# 5S.net
KiCad netlist of a schematic drawn in EAGLE
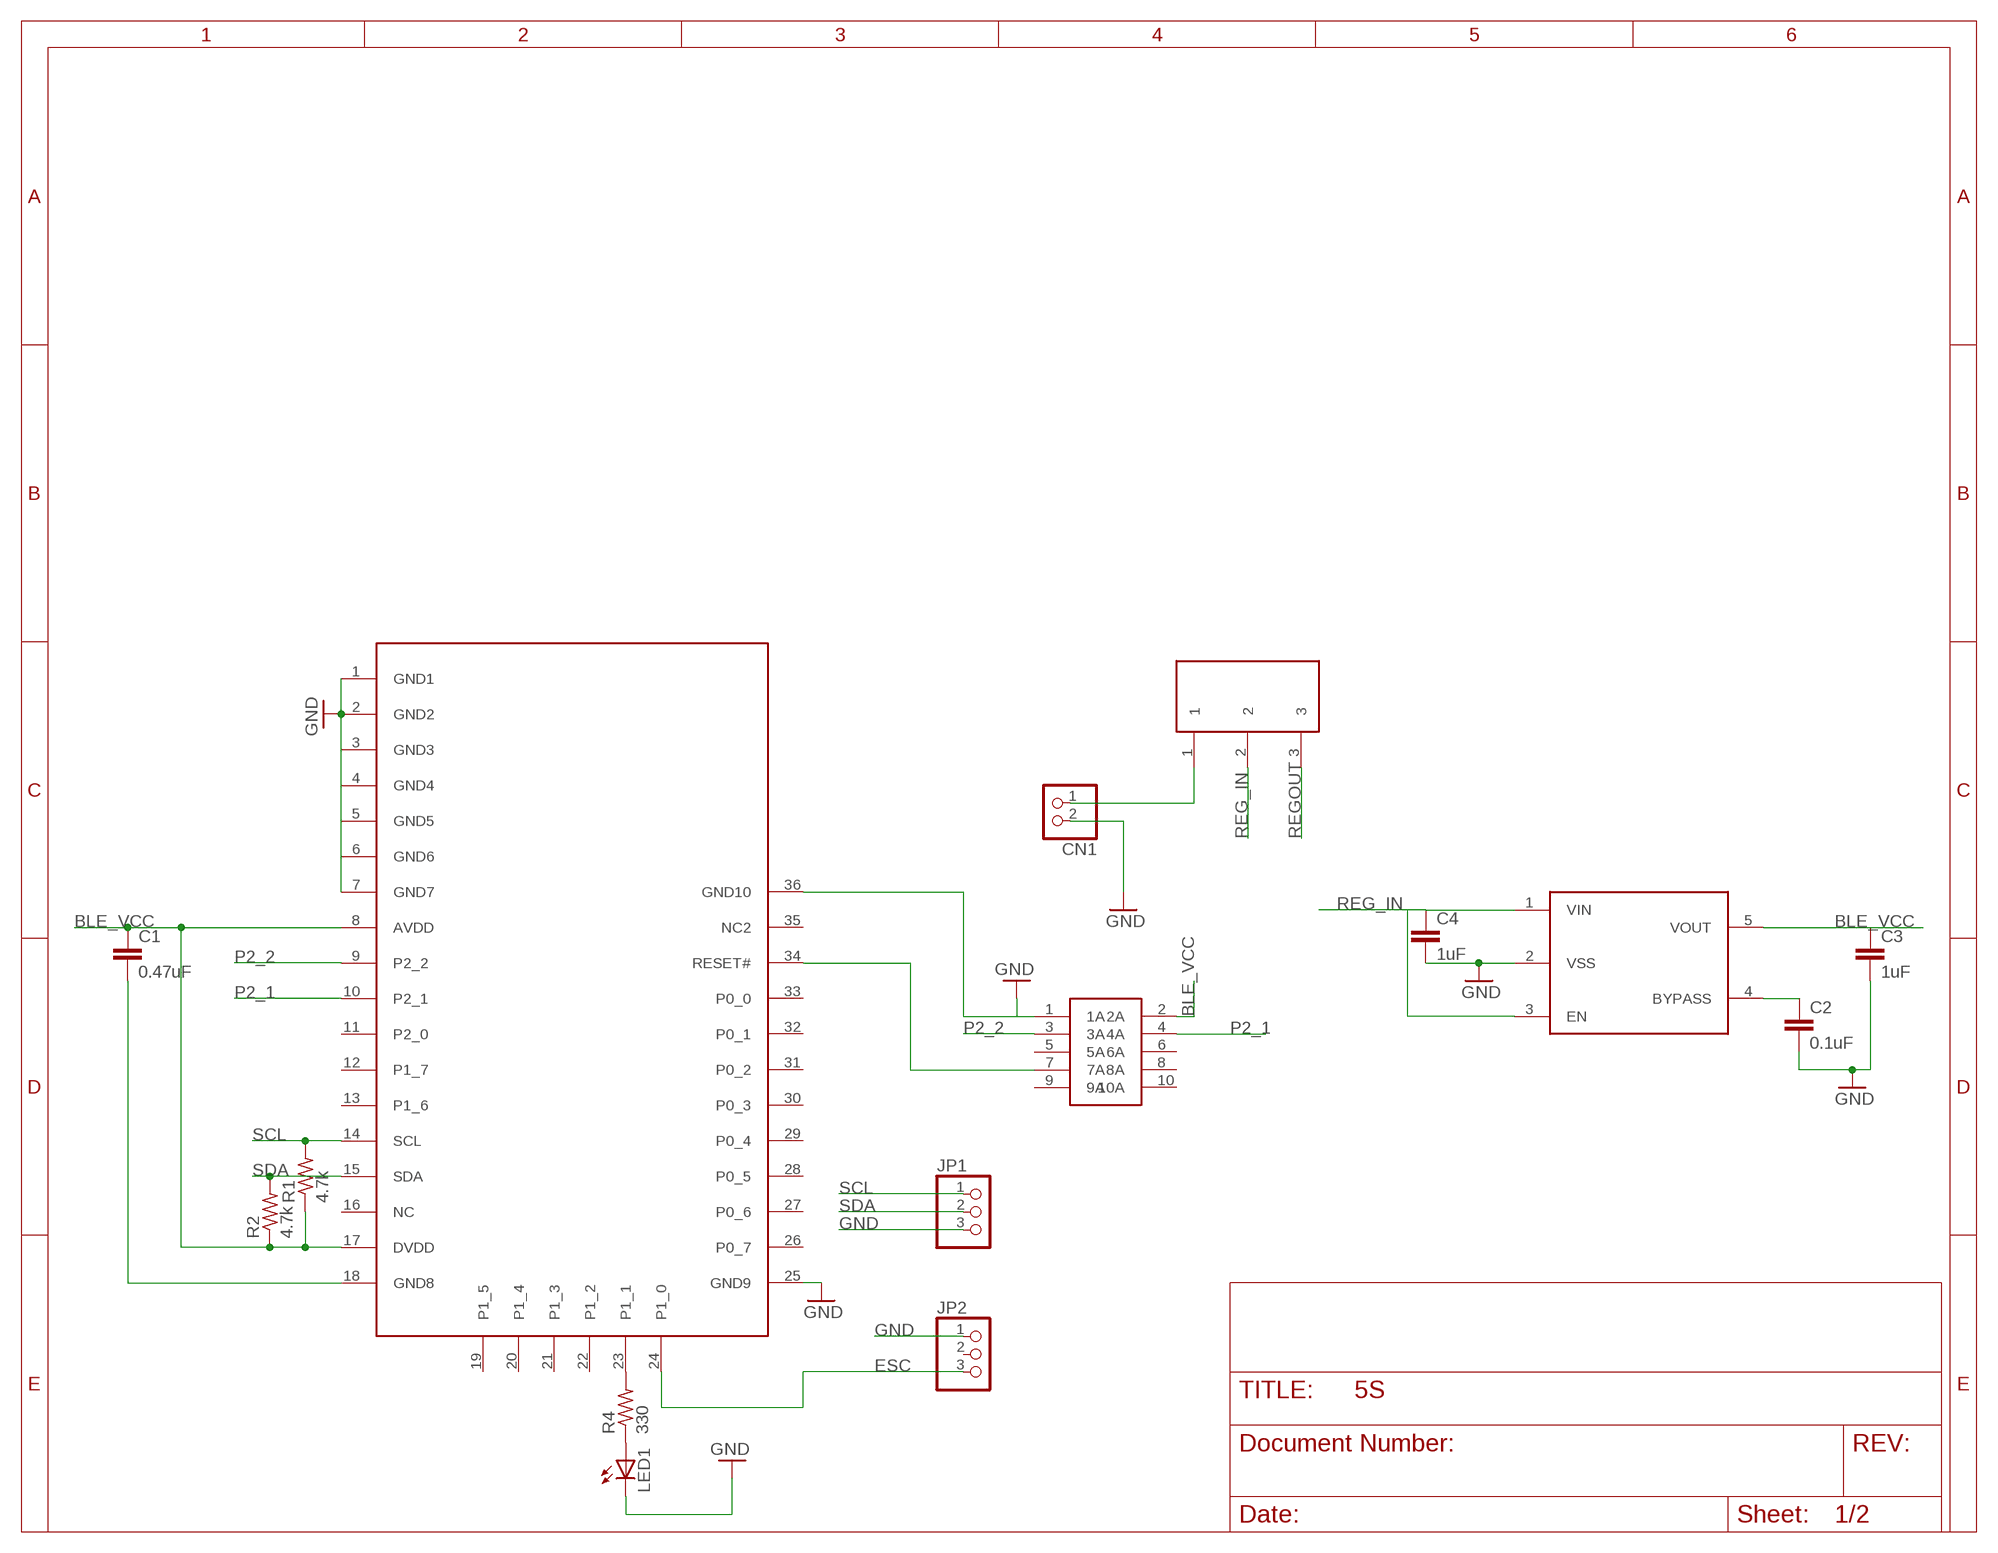
[diagram p0: schematic, sheet 1]
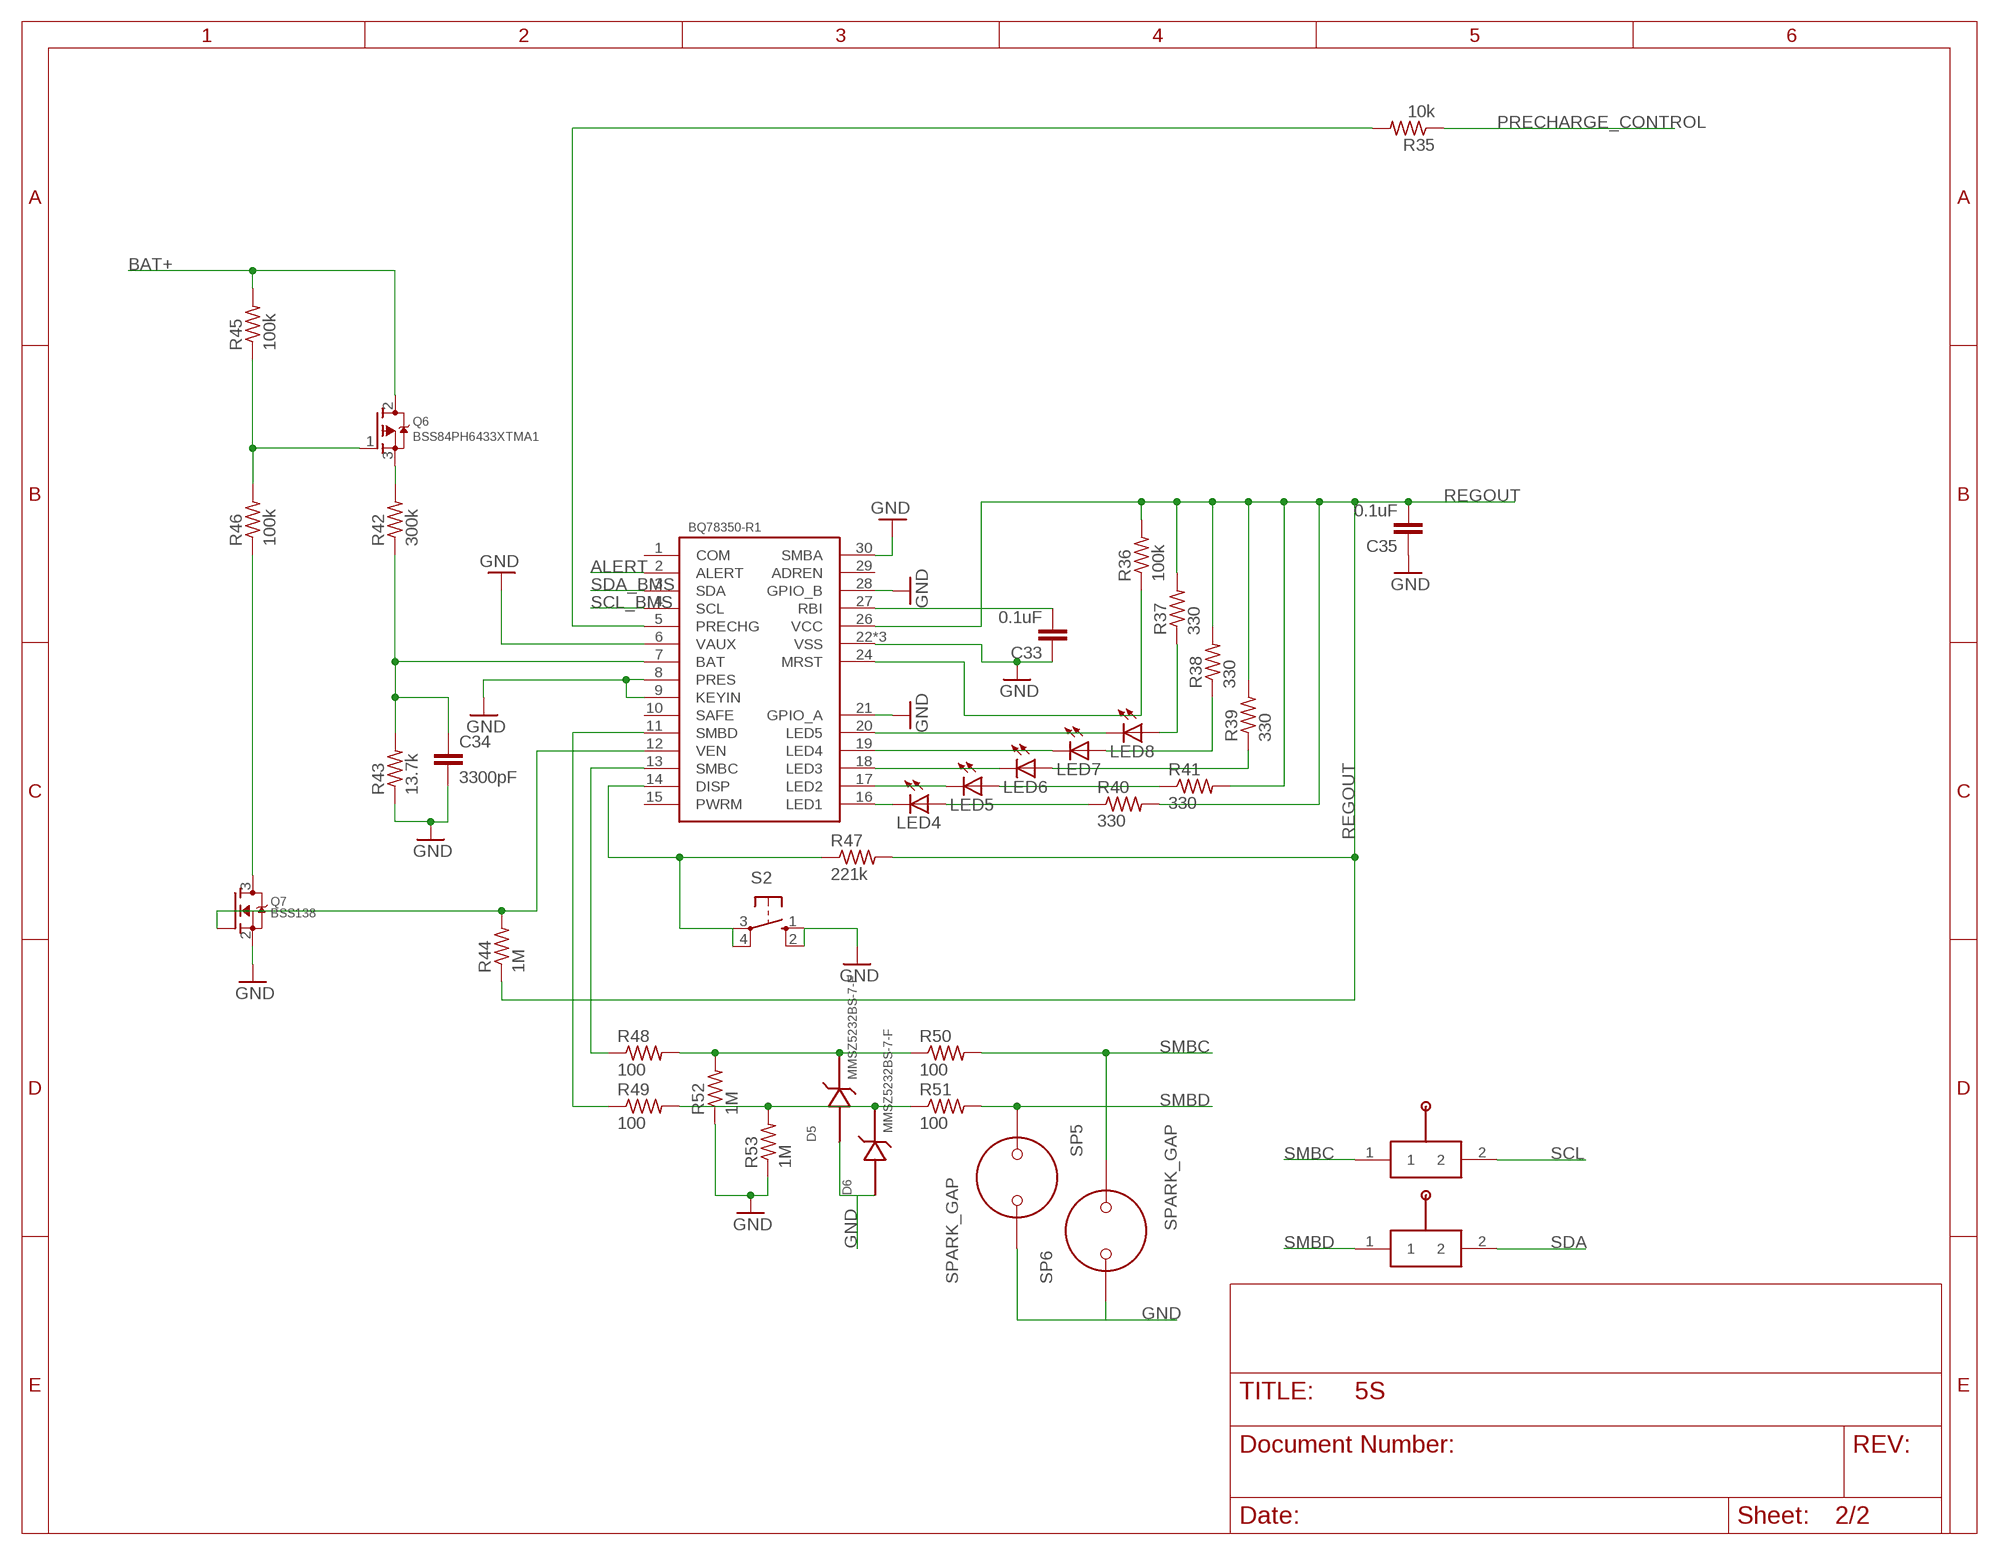
[diagram p1: schematic, sheet 2, part 1 of 2]
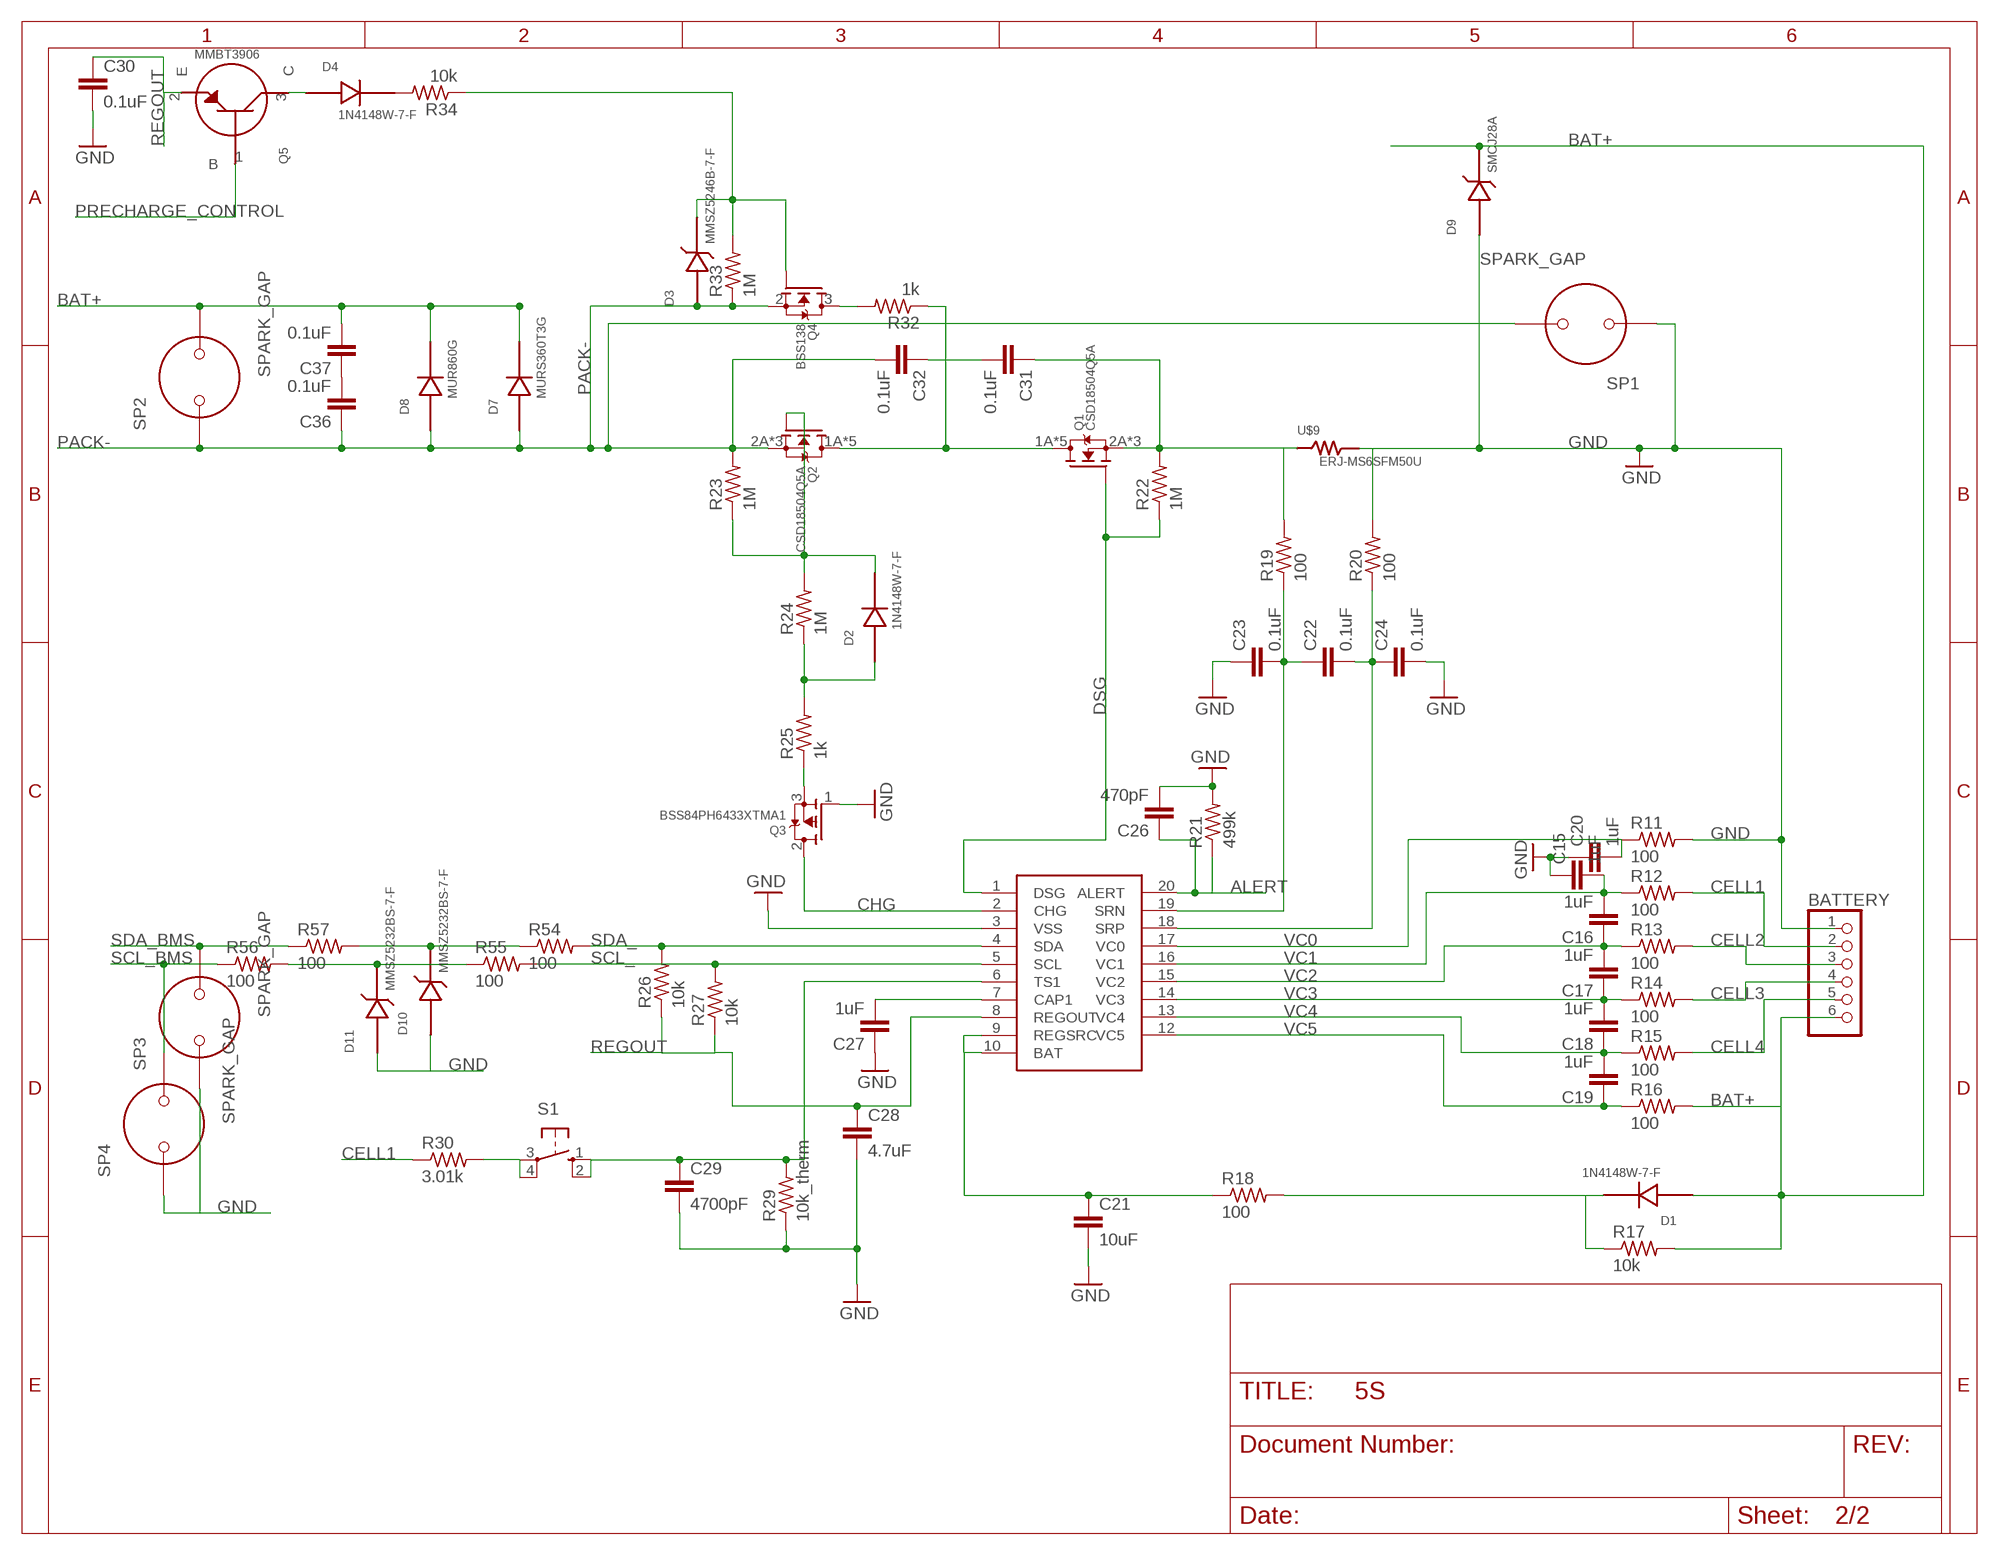
[diagram p2: schematic, sheet 2, part 2 of 2]

(export (version "E")
  (design (tool "Eeschema 10.0.6"))
  (components
    (comp (ref "C1")
      (value "0.47uF")
      (footprint "eagle-import:C0402")
      (libsource (lib "eagle-import") (part "C-EUC0402"))
    )
    (comp (ref "C2")
      (value "0.1uF")
      (footprint "eagle-import:C0402")
      (libsource (lib "eagle-import") (part "C-EUC0402"))
    )
    (comp (ref "C3")
      (value "1uF")
      (footprint "eagle-import:C0402")
      (libsource (lib "eagle-import") (part "C-EUC0402"))
    )
    (comp (ref "C4")
      (value "1uF")
      (footprint "eagle-import:C0402")
      (libsource (lib "eagle-import") (part "C-EUC0402"))
    )
    (comp (ref "CN1")
      (value "JST_2PIN-THM")
      (footprint "eagle-import:JST-PH-2-THM")
      (libsource (lib "eagle-import") (part "JST_2PIN-THM"))
    )
    (comp (ref "JP1")
      (value "PINHD-1X3")
      (footprint "eagle-import:1X03")
      (libsource (lib "eagle-import") (part "PINHD-1X3"))
    )
    (comp (ref "JP2")
      (value "PINHD-1X3")
      (footprint "eagle-import:1X03")
      (libsource (lib "eagle-import") (part "PINHD-1X3"))
    )
    (comp (ref "LED1")
      (value "LEDCHIP-LED0805")
      (footprint "eagle-import:CHIP-LED0805")
      (libsource (lib "eagle-import") (part "LEDCHIP-LED0805"))
    )
    (comp (ref "R1")
      (value "4.7k")
      (footprint "eagle-import:R0402")
      (libsource (lib "eagle-import") (part "R-US_R0402"))
    )
    (comp (ref "R2")
      (value "4.7k")
      (footprint "eagle-import:R0402")
      (libsource (lib "eagle-import") (part "R-US_R0402"))
    )
    (comp (ref "R4")
      (value "330")
      (footprint "eagle-import:R0402")
      (libsource (lib "eagle-import") (part "R-US_R0402"))
    )
    (comp (ref "U$1")
      (value "BLE113")
      (footprint "eagle-import:BLUEGIGA")
      (libsource (lib "eagle-import") (part "BLE113"))
    )
    (comp (ref "U$2")
      (value "RIBBON_10POS_MALE")
      (footprint "eagle-import:RIBBON_10POS_MALE")
      (libsource (lib "eagle-import") (part "RIBBON_10POS_MALE"))
    )
    (comp (ref "U$4")
      (value "SPDT_THRU")
      (footprint "eagle-import:SPDT_THRU")
      (libsource (lib "eagle-import") (part "SPDT_THRU"))
    )
    (comp (ref "U$5")
      (value "LP3985")
      (footprint "eagle-import:SOT23-5L")
      (libsource (lib "eagle-import") (part "LP3985"))
    )
    (comp (ref "BATTERY")
      (value "PINHD-1X6")
      (footprint "eagle-import:1X06")
      (libsource (lib "eagle-import") (part "PINHD-1X6"))
    )
    (comp (ref "C15")
      (value "1uF")
      (footprint "eagle-import:C0805")
      (libsource (lib "eagle-import") (part "C-EUC0805"))
    )
    (comp (ref "C16")
      (value "1uF")
      (footprint "eagle-import:C0805")
      (libsource (lib "eagle-import") (part "C-EUC0805"))
    )
    (comp (ref "C17")
      (value "1uF")
      (footprint "eagle-import:C0805")
      (libsource (lib "eagle-import") (part "C-EUC0805"))
    )
    (comp (ref "C18")
      (value "1uF")
      (footprint "eagle-import:C0805")
      (libsource (lib "eagle-import") (part "C-EUC0805"))
    )
    (comp (ref "C19")
      (value "1uF")
      (footprint "eagle-import:C0805")
      (libsource (lib "eagle-import") (part "C-EUC0805"))
    )
    (comp (ref "C20")
      (value "1uF")
      (footprint "eagle-import:C0805")
      (libsource (lib "eagle-import") (part "C-EUC0805"))
    )
    (comp (ref "C21")
      (value "10uF")
      (footprint "eagle-import:C1206")
      (libsource (lib "eagle-import") (part "C-EUC1206"))
    )
    (comp (ref "C22")
      (value "0.1uF")
      (footprint "eagle-import:C0805")
      (libsource (lib "eagle-import") (part "C-EUC0805"))
    )
    (comp (ref "C23")
      (value "0.1uF")
      (footprint "eagle-import:C0805")
      (libsource (lib "eagle-import") (part "C-EUC0805"))
    )
    (comp (ref "C24")
      (value "0.1uF")
      (footprint "eagle-import:C0805")
      (libsource (lib "eagle-import") (part "C-EUC0805"))
    )
    (comp (ref "C26")
      (value "470pF")
      (footprint "eagle-import:C0805")
      (libsource (lib "eagle-import") (part "C-EUC0805"))
    )
    (comp (ref "C27")
      (value "1uF")
      (footprint "eagle-import:C0805")
      (libsource (lib "eagle-import") (part "C-EUC0805"))
    )
    (comp (ref "C28")
      (value "4.7uF")
      (footprint "eagle-import:C0805")
      (libsource (lib "eagle-import") (part "C-EUC0805"))
    )
    (comp (ref "C29")
      (value "4700pF")
      (footprint "eagle-import:C0402")
      (libsource (lib "eagle-import") (part "C-EUC0402"))
    )
    (comp (ref "C30")
      (value "0.1uF")
      (footprint "eagle-import:C0805")
      (libsource (lib "eagle-import") (part "C-EUC0805"))
    )
    (comp (ref "C31")
      (value "0.1uF")
      (footprint "eagle-import:C0805")
      (libsource (lib "eagle-import") (part "C-EUC0805"))
    )
    (comp (ref "C32")
      (value "0.1uF")
      (footprint "eagle-import:C0805")
      (libsource (lib "eagle-import") (part "C-EUC0805"))
    )
    (comp (ref "C33")
      (value "0.1uF")
      (footprint "eagle-import:C0805")
      (libsource (lib "eagle-import") (part "C-EUC0805"))
    )
    (comp (ref "C34")
      (value "3300pF")
      (footprint "eagle-import:C0402")
      (libsource (lib "eagle-import") (part "C-EUC0402"))
    )
    (comp (ref "C35")
      (value "0.1uF")
      (footprint "eagle-import:C0805")
      (libsource (lib "eagle-import") (part "C-EUC0805"))
    )
    (comp (ref "C36")
      (value "0.1uF")
      (footprint "eagle-import:C0805")
      (libsource (lib "eagle-import") (part "C-EUC0805"))
    )
    (comp (ref "C37")
      (value "0.1uF")
      (footprint "eagle-import:C0805")
      (libsource (lib "eagle-import") (part "C-EUC0805"))
    )
    (comp (ref "D1")
      (value "1N4148W-7-F")
      (footprint "eagle-import:SOD-123")
      (libsource (lib "eagle-import") (part "1N4148W-7-F"))
    )
    (comp (ref "D2")
      (value "1N4148W-7-F")
      (footprint "eagle-import:SOD-123")
      (libsource (lib "eagle-import") (part "1N4148W-7-F"))
    )
    (comp (ref "D3")
      (value "MMSZ5246B-7-F")
      (footprint "eagle-import:SOD-123")
      (libsource (lib "eagle-import") (part "MMSZ5246B-7-F"))
    )
    (comp (ref "D4")
      (value "1N4148W-7-F")
      (footprint "eagle-import:SOD-123")
      (libsource (lib "eagle-import") (part "1N4148W-7-F"))
    )
    (comp (ref "D5")
      (value "MMSZ5232BS-7-F")
      (footprint "eagle-import:SOD-323F")
      (libsource (lib "eagle-import") (part "MMSZ5232BS-7-F"))
    )
    (comp (ref "D6")
      (value "MMSZ5232BS-7-F")
      (footprint "eagle-import:SOD-323F")
      (libsource (lib "eagle-import") (part "MMSZ5232BS-7-F"))
    )
    (comp (ref "D7")
      (value "MURS360T3G")
      (footprint "eagle-import:SMC(DO-214AB)")
      (libsource (lib "eagle-import") (part "MURS360T3G"))
    )
    (comp (ref "D8")
      (value "MUR860G")
      (footprint "eagle-import:TO-220(2RA)")
      (libsource (lib "eagle-import") (part "MUR860G"))
    )
    (comp (ref "D9")
      (value "SMCJ28A")
      (footprint "eagle-import:SMC(DO-214AB)")
      (libsource (lib "eagle-import") (part "SMCJ28A"))
    )
    (comp (ref "D10")
      (value "MMSZ5232BS-7-F")
      (footprint "eagle-import:SOD-323F")
      (libsource (lib "eagle-import") (part "MMSZ5232BS-7-F"))
    )
    (comp (ref "D11")
      (value "MMSZ5232BS-7-F")
      (footprint "eagle-import:SOD-323F")
      (libsource (lib "eagle-import") (part "MMSZ5232BS-7-F"))
    )
    (comp (ref "LED4")
      (value "LEDCHIPLED_0805")
      (footprint "eagle-import:CHIPLED_0805")
      (libsource (lib "eagle-import") (part "LEDCHIPLED_0805"))
    )
    (comp (ref "LED5")
      (value "LEDCHIPLED_0805")
      (footprint "eagle-import:CHIPLED_0805")
      (libsource (lib "eagle-import") (part "LEDCHIPLED_0805"))
    )
    (comp (ref "LED6")
      (value "LEDCHIPLED_0805")
      (footprint "eagle-import:CHIPLED_0805")
      (libsource (lib "eagle-import") (part "LEDCHIPLED_0805"))
    )
    (comp (ref "LED7")
      (value "LEDCHIPLED_0805")
      (footprint "eagle-import:CHIPLED_0805")
      (libsource (lib "eagle-import") (part "LEDCHIPLED_0805"))
    )
    (comp (ref "LED8")
      (value "LEDCHIPLED_0805")
      (footprint "eagle-import:CHIPLED_0805")
      (libsource (lib "eagle-import") (part "LEDCHIPLED_0805"))
    )
    (comp (ref "Q1")
      (value "CSD18504Q5A")
      (footprint "eagle-import:Q5A")
      (libsource (lib "eagle-import") (part "CSD18504Q5A"))
    )
    (comp (ref "Q2")
      (value "CSD18504Q5A")
      (footprint "eagle-import:Q5A")
      (libsource (lib "eagle-import") (part "CSD18504Q5A"))
    )
    (comp (ref "Q3")
      (value "BSS84PH6433XTMA1")
      (footprint "eagle-import:SOT23-3")
      (libsource (lib "eagle-import") (part "BSS84PH6433XTMA1"))
    )
    (comp (ref "Q4")
      (value "BSS138")
      (footprint "eagle-import:SOT23-3")
      (libsource (lib "eagle-import") (part "BSS138"))
    )
    (comp (ref "Q5")
      (value "MMBT3906")
      (footprint "eagle-import:SOT23-3")
      (libsource (lib "eagle-import") (part "MMBT3906"))
    )
    (comp (ref "Q6")
      (value "BSS84PH6433XTMA1")
      (footprint "eagle-import:SOT23-3")
      (libsource (lib "eagle-import") (part "BSS84PH6433XTMA1"))
    )
    (comp (ref "Q7")
      (value "BSS138")
      (footprint "eagle-import:SOT23-3")
      (libsource (lib "eagle-import") (part "BSS138"))
    )
    (comp (ref "R11")
      (value "100")
      (footprint "eagle-import:R1206")
      (libsource (lib "eagle-import") (part "R-US_R1206"))
    )
    (comp (ref "R12")
      (value "100")
      (footprint "eagle-import:R1206")
      (libsource (lib "eagle-import") (part "R-US_R1206"))
    )
    (comp (ref "R13")
      (value "100")
      (footprint "eagle-import:R1206")
      (libsource (lib "eagle-import") (part "R-US_R1206"))
    )
    (comp (ref "R14")
      (value "100")
      (footprint "eagle-import:R1206")
      (libsource (lib "eagle-import") (part "R-US_R1206"))
    )
    (comp (ref "R15")
      (value "100")
      (footprint "eagle-import:R1206")
      (libsource (lib "eagle-import") (part "R-US_R1206"))
    )
    (comp (ref "R16")
      (value "100")
      (footprint "eagle-import:R1206")
      (libsource (lib "eagle-import") (part "R-US_R1206"))
    )
    (comp (ref "R17")
      (value "10k")
      (footprint "eagle-import:R0805")
      (libsource (lib "eagle-import") (part "R-US_R0805"))
    )
    (comp (ref "R18")
      (value "100")
      (footprint "eagle-import:R0805")
      (libsource (lib "eagle-import") (part "R-US_R0805"))
    )
    (comp (ref "R19")
      (value "100")
      (footprint "eagle-import:R0805")
      (libsource (lib "eagle-import") (part "R-US_R0805"))
    )
    (comp (ref "R20")
      (value "100")
      (footprint "eagle-import:R0805")
      (libsource (lib "eagle-import") (part "R-US_R0805"))
    )
    (comp (ref "R21")
      (value "499k")
      (footprint "eagle-import:R0805")
      (libsource (lib "eagle-import") (part "R-US_R0805"))
    )
    (comp (ref "R22")
      (value "1M")
      (footprint "eagle-import:R1206")
      (libsource (lib "eagle-import") (part "R-US_R1206"))
    )
    (comp (ref "R23")
      (value "1M")
      (footprint "eagle-import:R1206")
      (libsource (lib "eagle-import") (part "R-US_R1206"))
    )
    (comp (ref "R24")
      (value "1M")
      (footprint "eagle-import:R1206")
      (libsource (lib "eagle-import") (part "R-US_R1206"))
    )
    (comp (ref "R25")
      (value "1k")
      (footprint "eagle-import:R0805")
      (libsource (lib "eagle-import") (part "R-US_R0805"))
    )
    (comp (ref "R26")
      (value "10k")
      (footprint "eagle-import:R0805")
      (libsource (lib "eagle-import") (part "R-US_R0805"))
    )
    (comp (ref "R27")
      (value "10k")
      (footprint "eagle-import:R0805")
      (libsource (lib "eagle-import") (part "R-US_R0805"))
    )
    (comp (ref "R29")
      (value "10k_therm")
      (footprint "eagle-import:R0402")
      (libsource (lib "eagle-import") (part "R-US_R0402"))
    )
    (comp (ref "R30")
      (value "3.01k")
      (footprint "eagle-import:R0805")
      (libsource (lib "eagle-import") (part "R-US_R0805"))
    )
    (comp (ref "R32")
      (value "1k")
      (footprint "eagle-import:R2512")
      (libsource (lib "eagle-import") (part "R-US_R2512"))
    )
    (comp (ref "R33")
      (value "1M")
      (footprint "eagle-import:R1206")
      (libsource (lib "eagle-import") (part "R-US_R1206"))
    )
    (comp (ref "R34")
      (value "10k")
      (footprint "eagle-import:R0805")
      (libsource (lib "eagle-import") (part "R-US_R0805"))
    )
    (comp (ref "R35")
      (value "10k")
      (footprint "eagle-import:R0805")
      (libsource (lib "eagle-import") (part "R-US_R0805"))
    )
    (comp (ref "R36")
      (value "100k")
      (footprint "eagle-import:R0805")
      (libsource (lib "eagle-import") (part "R-US_R0805"))
    )
    (comp (ref "R37")
      (value "330")
      (footprint "eagle-import:R0402")
      (libsource (lib "eagle-import") (part "R-US_R0402"))
    )
    (comp (ref "R38")
      (value "330")
      (footprint "eagle-import:R0402")
      (libsource (lib "eagle-import") (part "R-US_R0402"))
    )
    (comp (ref "R39")
      (value "330")
      (footprint "eagle-import:R0402")
      (libsource (lib "eagle-import") (part "R-US_R0402"))
    )
    (comp (ref "R40")
      (value "330")
      (footprint "eagle-import:R0402")
      (libsource (lib "eagle-import") (part "R-US_R0402"))
    )
    (comp (ref "R41")
      (value "330")
      (footprint "eagle-import:R0402")
      (libsource (lib "eagle-import") (part "R-US_R0402"))
    )
    (comp (ref "R42")
      (value "300k")
      (footprint "eagle-import:R0805")
      (libsource (lib "eagle-import") (part "R-US_R0805"))
    )
    (comp (ref "R43")
      (value "13.7k")
      (footprint "eagle-import:R0805")
      (libsource (lib "eagle-import") (part "R-US_R0805"))
    )
    (comp (ref "R44")
      (value "1M")
      (footprint "eagle-import:R1206")
      (libsource (lib "eagle-import") (part "R-US_R1206"))
    )
    (comp (ref "R45")
      (value "100k")
      (footprint "eagle-import:R0805")
      (libsource (lib "eagle-import") (part "R-US_R0805"))
    )
    (comp (ref "R46")
      (value "100k")
      (footprint "eagle-import:R0805")
      (libsource (lib "eagle-import") (part "R-US_R0805"))
    )
    (comp (ref "R47")
      (value "221k")
      (footprint "eagle-import:R0805")
      (libsource (lib "eagle-import") (part "R-US_R0805"))
    )
    (comp (ref "R48")
      (value "100")
      (footprint "eagle-import:R0805")
      (libsource (lib "eagle-import") (part "R-US_R0805"))
    )
    (comp (ref "R49")
      (value "100")
      (footprint "eagle-import:R0805")
      (libsource (lib "eagle-import") (part "R-US_R0805"))
    )
    (comp (ref "R50")
      (value "100")
      (footprint "eagle-import:R0805")
      (libsource (lib "eagle-import") (part "R-US_R0805"))
    )
    (comp (ref "R51")
      (value "100")
      (footprint "eagle-import:R0805")
      (libsource (lib "eagle-import") (part "R-US_R0805"))
    )
    (comp (ref "R52")
      (value "1M")
      (footprint "eagle-import:R1206")
      (libsource (lib "eagle-import") (part "R-US_R1206"))
    )
    (comp (ref "R53")
      (value "1M")
      (footprint "eagle-import:R1206")
      (libsource (lib "eagle-import") (part "R-US_R1206"))
    )
    (comp (ref "R54")
      (value "100")
      (footprint "eagle-import:R0805")
      (libsource (lib "eagle-import") (part "R-US_R0805"))
    )
    (comp (ref "R55")
      (value "100")
      (footprint "eagle-import:R0805")
      (libsource (lib "eagle-import") (part "R-US_R0805"))
    )
    (comp (ref "R56")
      (value "100")
      (footprint "eagle-import:R0805")
      (libsource (lib "eagle-import") (part "R-US_R0805"))
    )
    (comp (ref "R57")
      (value "100")
      (footprint "eagle-import:R0805")
      (libsource (lib "eagle-import") (part "R-US_R0805"))
    )
    (comp (ref "S1")
      (value "10-XX")
      (footprint "eagle-import:B3F-10XX")
      (fields (field (name "MPN") "B3F-1000"))
      (libsource (lib "eagle-import") (part "10-XX"))
    )
    (comp (ref "S2")
      (value "10-XX")
      (footprint "eagle-import:B3F-10XX")
      (fields (field (name "MPN") "B3F-1000"))
      (libsource (lib "eagle-import") (part "10-XX"))
    )
    (comp (ref "SP1")
      (value "SPARK_GAP")
      (footprint "eagle-import:SPARK_GAP")
      (libsource (lib "eagle-import") (part "SPARK_GAP"))
    )
    (comp (ref "SP2")
      (value "SPARK_GAP")
      (footprint "eagle-import:SPARK_GAP")
      (libsource (lib "eagle-import") (part "SPARK_GAP"))
    )
    (comp (ref "SP3")
      (value "SPARK_GAP")
      (footprint "eagle-import:SPARK_GAP")
      (libsource (lib "eagle-import") (part "SPARK_GAP"))
    )
    (comp (ref "SP4")
      (value "SPARK_GAP")
      (footprint "eagle-import:SPARK_GAP")
      (libsource (lib "eagle-import") (part "SPARK_GAP"))
    )
    (comp (ref "SP5")
      (value "SPARK_GAP")
      (footprint "eagle-import:SPARK_GAP")
      (libsource (lib "eagle-import") (part "SPARK_GAP"))
    )
    (comp (ref "SP6")
      (value "SPARK_GAP")
      (footprint "eagle-import:SPARK_GAP")
      (libsource (lib "eagle-import") (part "SPARK_GAP"))
    )
    (comp (ref "U$3")
      (value "BQ76920")
      (footprint "eagle-import:SOIC-20")
      (libsource (lib "eagle-import") (part "BQ76920"))
    )
    (comp (ref "U$9")
      (value "ERJ-MS6SFM50U")
      (footprint "eagle-import:ERJ-MS6SFM50U")
      (libsource (lib "eagle-import") (part "ERJ-MS6SFM50U"))
    )
    (comp (ref "U$10")
      (value "BQ78350-R1")
      (footprint "eagle-import:SOIC-30")
      (libsource (lib "eagle-import") (part "BQ78350-R1"))
    )
    (comp (ref "U$16")
      (value "MANUAL_SWITCH")
      (footprint "eagle-import:MANUAL_SWITCH")
      (libsource (lib "eagle-import") (part "MANUAL_SWITCH"))
    )
    (comp (ref "U$17")
      (value "MANUAL_SWITCH")
      (footprint "eagle-import:MANUAL_SWITCH")
      (libsource (lib "eagle-import") (part "MANUAL_SWITCH"))
    )
  )
  (nets
    (net (code "1") (name "ALERT") (class "Default")
      (node (ref "C26") (pin "1") (pinfunction "1_1") (pintype "passive"))
      (node (ref "R21") (pin "1") (pinfunction "1_1") (pintype "passive"))
      (node (ref "U$10") (pin "2") (pinfunction "ALERT_2") (pintype "bidirectional"))
      (node (ref "U$3") (pin "20") (pinfunction "ALERT_20") (pintype "bidirectional"))
    )
    (net (code "2") (name "BAT+") (class "Default")
      (node (ref "BATTERY") (pin "6") (pinfunction "6_6") (pintype "passive"))
      (node (ref "C37") (pin "2") (pinfunction "2_2") (pintype "passive"))
      (node (ref "D1") (pin "P$1") (pinfunction "P$1_P$1") (pintype "bidirectional"))
      (node (ref "D7") (pin "2") (pinfunction "P$2_2") (pintype "bidirectional"))
      (node (ref "D8") (pin "P$3") (pinfunction "P$2_P$3") (pintype "bidirectional"))
      (node (ref "D9") (pin "2") (pinfunction "2_2") (pintype "bidirectional"))
      (node (ref "Q6") (pin "2") (pinfunction "S_2") (pintype "bidirectional"))
      (node (ref "R16") (pin "2") (pinfunction "2_2") (pintype "passive"))
      (node (ref "R17") (pin "2") (pinfunction "2_2") (pintype "passive"))
      (node (ref "R45") (pin "2") (pinfunction "2_2") (pintype "passive"))
      (node (ref "SP2") (pin "P$2") (pinfunction "P$2_P$2") (pintype "bidirectional"))
    )
    (net (code "3") (name "BLE_VCC") (class "Default")
      (node (ref "C1") (pin "1") (pinfunction "1_1") (pintype "passive"))
      (node (ref "C3") (pin "1") (pinfunction "1_1") (pintype "passive"))
      (node (ref "R1") (pin "1") (pinfunction "1_1") (pintype "passive"))
      (node (ref "R2") (pin "1") (pinfunction "1_1") (pintype "passive"))
      (node (ref "U$1") (pin "17") (pinfunction "DVDD_17") (pintype "bidirectional"))
      (node (ref "U$1") (pin "8") (pinfunction "AVDD_8") (pintype "bidirectional"))
      (node (ref "U$2") (pin "2") (pinfunction "2A_2") (pintype "bidirectional"))
      (node (ref "U$5") (pin "5") (pinfunction "VOUT_5") (pintype "bidirectional"))
    )
    (net (code "4") (name "CELL1") (class "Default")
      (node (ref "BATTERY") (pin "2") (pinfunction "2_2") (pintype "passive"))
      (node (ref "R12") (pin "2") (pinfunction "2_2") (pintype "passive"))
      (node (ref "R30") (pin "1") (pinfunction "1_1") (pintype "passive"))
    )
    (net (code "5") (name "CELL2") (class "Default")
      (node (ref "BATTERY") (pin "3") (pinfunction "3_3") (pintype "passive"))
      (node (ref "R13") (pin "2") (pinfunction "2_2") (pintype "passive"))
    )
    (net (code "6") (name "CELL3") (class "Default")
      (node (ref "BATTERY") (pin "4") (pinfunction "4_4") (pintype "passive"))
      (node (ref "R14") (pin "2") (pinfunction "2_2") (pintype "passive"))
    )
    (net (code "7") (name "CELL4") (class "Default")
      (node (ref "BATTERY") (pin "5") (pinfunction "5_5") (pintype "passive"))
      (node (ref "R15") (pin "2") (pinfunction "2_2") (pintype "passive"))
    )
    (net (code "8") (name "CHG") (class "Default")
      (node (ref "Q3") (pin "2") (pinfunction "S_2") (pintype "bidirectional"))
      (node (ref "U$3") (pin "2") (pinfunction "CHG_2") (pintype "bidirectional"))
    )
    (net (code "9") (name "DSG") (class "Default")
      (node (ref "Q1") (pin "3A") (pinfunction "G_3A") (pintype "bidirectional"))
      (node (ref "R22") (pin "1") (pinfunction "1_1") (pintype "passive"))
      (node (ref "U$3") (pin "1") (pinfunction "DSG_1") (pintype "bidirectional"))
    )
    (net (code "10") (name "ESC") (class "Default")
      (node (ref "JP2") (pin "3") (pinfunction "3_3") (pintype "passive"))
      (node (ref "U$1") (pin "24") (pinfunction "P1_0_24") (pintype "bidirectional"))
    )
    (net (code "11") (name "GND") (class "Default")
      (node (ref "BATTERY") (pin "1") (pinfunction "1_1") (pintype "passive"))
      (node (ref "C15") (pin "1") (pinfunction "1_1") (pintype "passive"))
      (node (ref "C2") (pin "2") (pinfunction "2_2") (pintype "passive"))
      (node (ref "C20") (pin "1") (pinfunction "1_1") (pintype "passive"))
      (node (ref "C21") (pin "2") (pinfunction "2_2") (pintype "passive"))
      (node (ref "C23") (pin "1") (pinfunction "1_1") (pintype "passive"))
      (node (ref "C24") (pin "2") (pinfunction "2_2") (pintype "passive"))
      (node (ref "C26") (pin "2") (pinfunction "2_2") (pintype "passive"))
      (node (ref "C27") (pin "1") (pinfunction "1_1") (pintype "passive"))
      (node (ref "C28") (pin "2") (pinfunction "2_2") (pintype "passive"))
      (node (ref "C29") (pin "2") (pinfunction "2_2") (pintype "passive"))
      (node (ref "C3") (pin "2") (pinfunction "2_2") (pintype "passive"))
      (node (ref "C30") (pin "2") (pinfunction "2_2") (pintype "passive"))
      (node (ref "C33") (pin "1") (pinfunction "1_1") (pintype "passive"))
      (node (ref "C34") (pin "2") (pinfunction "2_2") (pintype "passive"))
      (node (ref "C35") (pin "1") (pinfunction "1_1") (pintype "passive"))
      (node (ref "C4") (pin "2") (pinfunction "2_2") (pintype "passive"))
      (node (ref "CN1") (pin "2") (pinfunction "1_2") (pintype "passive"))
      (node (ref "D10") (pin "1") (pinfunction "1_1") (pintype "bidirectional"))
      (node (ref "D11") (pin "1") (pinfunction "1_1") (pintype "bidirectional"))
      (node (ref "D5") (pin "1") (pinfunction "1_1") (pintype "bidirectional"))
      (node (ref "D6") (pin "1") (pinfunction "1_1") (pintype "bidirectional"))
      (node (ref "D9") (pin "1") (pinfunction "1_1") (pintype "bidirectional"))
      (node (ref "JP1") (pin "3") (pinfunction "3_3") (pintype "passive"))
      (node (ref "JP2") (pin "1") (pinfunction "1_1") (pintype "passive"))
      (node (ref "LED1") (pin "C") (pinfunction "C_C") (pintype "passive"))
      (node (ref "Q3") (pin "1") (pinfunction "G_1") (pintype "bidirectional"))
      (node (ref "Q7") (pin "2") (pinfunction "S_2") (pintype "bidirectional"))
      (node (ref "R11") (pin "2") (pinfunction "2_2") (pintype "passive"))
      (node (ref "R20") (pin "2") (pinfunction "2_2") (pintype "passive"))
      (node (ref "R21") (pin "2") (pinfunction "2_2") (pintype "passive"))
      (node (ref "R29") (pin "1") (pinfunction "1_1") (pintype "passive"))
      (node (ref "R43") (pin "1") (pinfunction "1_1") (pintype "passive"))
      (node (ref "R52") (pin "1") (pinfunction "1_1") (pintype "passive"))
      (node (ref "R53") (pin "1") (pinfunction "1_1") (pintype "passive"))
      (node (ref "S2") (pin "1") (pinfunction "S_1") (pintype "passive"))
      (node (ref "S2") (pin "2") (pinfunction "S1_2") (pintype "passive"))
      (node (ref "SP1") (pin "P$1") (pinfunction "P$1_P$1") (pintype "bidirectional"))
      (node (ref "SP3") (pin "P$1") (pinfunction "P$1_P$1") (pintype "bidirectional"))
      (node (ref "SP4") (pin "P$1") (pinfunction "P$1_P$1") (pintype "bidirectional"))
      (node (ref "SP5") (pin "P$2") (pinfunction "P$2_P$2") (pintype "bidirectional"))
      (node (ref "SP6") (pin "P$1") (pinfunction "P$1_P$1") (pintype "bidirectional"))
      (node (ref "U$1") (pin "1") (pinfunction "GND1_1") (pintype "bidirectional"))
      (node (ref "U$1") (pin "2") (pinfunction "GND2_2") (pintype "bidirectional"))
      (node (ref "U$1") (pin "25") (pinfunction "GND9_25") (pintype "bidirectional"))
      (node (ref "U$1") (pin "3") (pinfunction "GND3_3") (pintype "bidirectional"))
      (node (ref "U$1") (pin "36") (pinfunction "GND10_36") (pintype "bidirectional"))
      (node (ref "U$1") (pin "4") (pinfunction "GND4_4") (pintype "bidirectional"))
      (node (ref "U$1") (pin "5") (pinfunction "GND5_5") (pintype "bidirectional"))
      (node (ref "U$1") (pin "6") (pinfunction "GND6_6") (pintype "bidirectional"))
      (node (ref "U$1") (pin "7") (pinfunction "GND7_7") (pintype "bidirectional"))
      (node (ref "U$10") (pin "21") (pinfunction "GPIO_A_21") (pintype "bidirectional"))
      (node (ref "U$10") (pin "22") (pinfunction "VSS_22") (pintype "bidirectional"))
      (node (ref "U$10") (pin "23") (pinfunction "VSS_23") (pintype "bidirectional"))
      (node (ref "U$10") (pin "25") (pinfunction "VSS_25") (pintype "bidirectional"))
      (node (ref "U$10") (pin "28") (pinfunction "GPIO_B_28") (pintype "bidirectional"))
      (node (ref "U$10") (pin "30") (pinfunction "SMBA_30") (pintype "bidirectional"))
      (node (ref "U$10") (pin "6") (pinfunction "VAUX_6") (pintype "bidirectional"))
      (node (ref "U$10") (pin "8") (pinfunction "PRES_8") (pintype "bidirectional"))
      (node (ref "U$10") (pin "9") (pinfunction "KEYIN_9") (pintype "bidirectional"))
      (node (ref "U$2") (pin "1") (pinfunction "1A_1") (pintype "bidirectional"))
      (node (ref "U$3") (pin "3") (pinfunction "VSS_3") (pintype "bidirectional"))
      (node (ref "U$5") (pin "2") (pinfunction "VSS_2") (pintype "bidirectional"))
      (node (ref "U$9") (pin "2") (pinfunction "P$2_2") (pintype "bidirectional"))
    )
    (net (code "12") (name "Net-(C31-Pad2)") (class "Default")
      (node (ref "C31") (pin "2") (pinfunction "2_2") (pintype "passive"))
      (node (ref "C32") (pin "1") (pinfunction "1_1") (pintype "passive"))
    )
    (net (code "13") (name "Net-(C36-Pad2)") (class "Default")
      (node (ref "C36") (pin "2") (pinfunction "2_2") (pintype "passive"))
      (node (ref "C37") (pin "1") (pinfunction "1_1") (pintype "passive"))
    )
    (net (code "14") (name "Net-(CN1-2)") (class "Default")
      (node (ref "CN1") (pin "1") (pinfunction "2_1") (pintype "passive"))
      (node (ref "U$4") (pin "1") (pinfunction "1_1") (pintype "bidirectional"))
    )
    (net (code "15") (name "Net-(D1-PadP$2)") (class "Default")
      (node (ref "D1") (pin "P$2") (pinfunction "P$2_P$2") (pintype "bidirectional"))
      (node (ref "R17") (pin "1") (pinfunction "1_1") (pintype "passive"))
      (node (ref "R18") (pin "2") (pinfunction "2_2") (pintype "passive"))
    )
    (net (code "16") (name "Net-(D2-PadP$1)") (class "Default")
      (node (ref "D2") (pin "P$1") (pinfunction "P$1_P$1") (pintype "bidirectional"))
      (node (ref "R24") (pin "1") (pinfunction "1_1") (pintype "passive"))
      (node (ref "R25") (pin "2") (pinfunction "2_2") (pintype "passive"))
    )
    (net (code "17") (name "Net-(D3-2)") (class "Default")
      (node (ref "D3") (pin "P$2") (pinfunction "2_P$2") (pintype "bidirectional"))
      (node (ref "Q4") (pin "1") (pinfunction "G_1") (pintype "bidirectional"))
      (node (ref "R33") (pin "2") (pinfunction "2_2") (pintype "passive"))
      (node (ref "R34") (pin "1") (pinfunction "1_1") (pintype "passive"))
    )
    (net (code "18") (name "Net-(D4-PadP$2)") (class "Default")
      (node (ref "D4") (pin "P$2") (pinfunction "P$2_P$2") (pintype "bidirectional"))
      (node (ref "R34") (pin "2") (pinfunction "2_2") (pintype "passive"))
    )
    (net (code "19") (name "Net-(D5-Pad2)") (class "Default")
      (node (ref "D5") (pin "2") (pinfunction "2_2") (pintype "bidirectional"))
      (node (ref "R48") (pin "2") (pinfunction "2_2") (pintype "passive"))
      (node (ref "R50") (pin "1") (pinfunction "1_1") (pintype "passive"))
      (node (ref "R52") (pin "2") (pinfunction "2_2") (pintype "passive"))
    )
    (net (code "20") (name "Net-(D6-Pad2)") (class "Default")
      (node (ref "D6") (pin "2") (pinfunction "2_2") (pintype "bidirectional"))
      (node (ref "R49") (pin "2") (pinfunction "2_2") (pintype "passive"))
      (node (ref "R51") (pin "1") (pinfunction "1_1") (pintype "passive"))
      (node (ref "R53") (pin "2") (pinfunction "2_2") (pintype "passive"))
    )
    (net (code "21") (name "Net-(D10-Pad2)") (class "Default")
      (node (ref "D10") (pin "2") (pinfunction "2_2") (pintype "bidirectional"))
      (node (ref "R54") (pin "1") (pinfunction "1_1") (pintype "passive"))
      (node (ref "R57") (pin "2") (pinfunction "2_2") (pintype "passive"))
    )
    (net (code "22") (name "Net-(D11-Pad2)") (class "Default")
      (node (ref "D11") (pin "2") (pinfunction "2_2") (pintype "bidirectional"))
      (node (ref "R55") (pin "1") (pinfunction "1_1") (pintype "passive"))
      (node (ref "R56") (pin "2") (pinfunction "2_2") (pintype "passive"))
    )
    (net (code "23") (name "Net-(LED1-PadA)") (class "Default")
      (node (ref "LED1") (pin "A") (pinfunction "A_A") (pintype "passive"))
      (node (ref "R4") (pin "1") (pinfunction "1_1") (pintype "passive"))
    )
    (net (code "24") (name "Net-(LED4-PadA)") (class "Default")
      (node (ref "LED4") (pin "A") (pinfunction "A_A") (pintype "passive"))
      (node (ref "R40") (pin "1") (pinfunction "1_1") (pintype "passive"))
    )
    (net (code "25") (name "Net-(LED5-PadA)") (class "Default")
      (node (ref "LED5") (pin "A") (pinfunction "A_A") (pintype "passive"))
      (node (ref "R41") (pin "1") (pinfunction "1_1") (pintype "passive"))
    )
    (net (code "26") (name "Net-(LED6-PadA)") (class "Default")
      (node (ref "LED6") (pin "A") (pinfunction "A_A") (pintype "passive"))
      (node (ref "R39") (pin "1") (pinfunction "1_1") (pintype "passive"))
    )
    (net (code "27") (name "Net-(LED7-PadA)") (class "Default")
      (node (ref "LED7") (pin "A") (pinfunction "A_A") (pintype "passive"))
      (node (ref "R38") (pin "1") (pinfunction "1_1") (pintype "passive"))
    )
    (net (code "28") (name "Net-(LED8-PadA)") (class "Default")
      (node (ref "LED8") (pin "A") (pinfunction "A_A") (pintype "passive"))
      (node (ref "R37") (pin "1") (pinfunction "1_1") (pintype "passive"))
    )
    (net (code "29") (name "Net-(Q1-D-Pad1A)") (class "Default")
      (node (ref "Q1") (pin "1A") (pinfunction "D_1A") (pintype "bidirectional"))
      (node (ref "Q1") (pin "1B") (pinfunction "D_1B") (pintype "bidirectional"))
      (node (ref "Q1") (pin "1C") (pinfunction "D_1C") (pintype "bidirectional"))
      (node (ref "Q1") (pin "1D") (pinfunction "D_1D") (pintype "bidirectional"))
      (node (ref "Q1") (pin "1E") (pinfunction "D_1E") (pintype "bidirectional"))
      (node (ref "Q2") (pin "1A") (pinfunction "D_1A") (pintype "bidirectional"))
      (node (ref "Q2") (pin "1B") (pinfunction "D_1B") (pintype "bidirectional"))
      (node (ref "Q2") (pin "1C") (pinfunction "D_1C") (pintype "bidirectional"))
      (node (ref "Q2") (pin "1D") (pinfunction "D_1D") (pintype "bidirectional"))
      (node (ref "Q2") (pin "1E") (pinfunction "D_1E") (pintype "bidirectional"))
      (node (ref "R32") (pin "1") (pinfunction "1_1") (pintype "passive"))
    )
    (net (code "30") (name "Net-(Q2-G)") (class "Default")
      (node (ref "D2") (pin "P$2") (pinfunction "P$2_P$2") (pintype "bidirectional"))
      (node (ref "Q2") (pin "3A") (pinfunction "G_3A") (pintype "bidirectional"))
      (node (ref "R23") (pin "1") (pinfunction "1_1") (pintype "passive"))
      (node (ref "R24") (pin "2") (pinfunction "2_2") (pintype "passive"))
    )
    (net (code "31") (name "Net-(Q3-D)") (class "Default")
      (node (ref "Q3") (pin "3") (pinfunction "D_3") (pintype "bidirectional"))
      (node (ref "R25") (pin "1") (pinfunction "1_1") (pintype "passive"))
    )
    (net (code "32") (name "Net-(Q4-D)") (class "Default")
      (node (ref "Q4") (pin "3") (pinfunction "D_3") (pintype "bidirectional"))
      (node (ref "R32") (pin "2") (pinfunction "2_2") (pintype "passive"))
    )
    (net (code "33") (name "Net-(Q5-C)") (class "Default")
      (node (ref "D4") (pin "P$1") (pinfunction "P$1_P$1") (pintype "bidirectional"))
      (node (ref "Q5") (pin "3") (pinfunction "C_3") (pintype "bidirectional"))
    )
    (net (code "34") (name "Net-(Q6-D)") (class "Default")
      (node (ref "Q6") (pin "3") (pinfunction "D_3") (pintype "bidirectional"))
      (node (ref "R42") (pin "2") (pinfunction "2_2") (pintype "passive"))
    )
    (net (code "35") (name "Net-(Q6-G)") (class "Default")
      (node (ref "Q6") (pin "1") (pinfunction "G_1") (pintype "bidirectional"))
      (node (ref "R45") (pin "1") (pinfunction "1_1") (pintype "passive"))
      (node (ref "R46") (pin "2") (pinfunction "2_2") (pintype "passive"))
    )
    (net (code "36") (name "Net-(Q7-D)") (class "Default")
      (node (ref "Q7") (pin "3") (pinfunction "D_3") (pintype "bidirectional"))
      (node (ref "R46") (pin "1") (pinfunction "1_1") (pintype "passive"))
    )
    (net (code "37") (name "Net-(Q7-G)") (class "Default")
      (node (ref "Q7") (pin "1") (pinfunction "G_1") (pintype "bidirectional"))
      (node (ref "R44") (pin "2") (pinfunction "2_2") (pintype "passive"))
      (node (ref "U$10") (pin "12") (pinfunction "VEN_12") (pintype "bidirectional"))
    )
    (net (code "38") (name "Net-(S1-P)") (class "Default")
      (node (ref "R30") (pin "2") (pinfunction "2_2") (pintype "passive"))
      (node (ref "S1") (pin "3") (pinfunction "P_3") (pintype "passive"))
      (node (ref "S1") (pin "4") (pinfunction "P1_4") (pintype "passive"))
    )
    (net (code "39") (name "Net-(S1-S)") (class "Default")
      (node (ref "C29") (pin "1") (pinfunction "1_1") (pintype "passive"))
      (node (ref "R29") (pin "2") (pinfunction "2_2") (pintype "passive"))
      (node (ref "S1") (pin "1") (pinfunction "S_1") (pintype "passive"))
      (node (ref "S1") (pin "2") (pinfunction "S1_2") (pintype "passive"))
      (node (ref "U$3") (pin "6") (pinfunction "TS1_6") (pintype "bidirectional"))
    )
    (net (code "40") (name "Net-(S2-P)") (class "Default")
      (node (ref "R47") (pin "1") (pinfunction "1_1") (pintype "passive"))
      (node (ref "S2") (pin "3") (pinfunction "P_3") (pintype "passive"))
      (node (ref "S2") (pin "4") (pinfunction "P1_4") (pintype "passive"))
      (node (ref "U$10") (pin "14") (pinfunction "DISP_14") (pintype "bidirectional"))
    )
    (net (code "41") (name "Net-(U$1-GND8)") (class "Default")
      (node (ref "C1") (pin "2") (pinfunction "2_2") (pintype "passive"))
      (node (ref "U$1") (pin "18") (pinfunction "GND8_18") (pintype "bidirectional"))
    )
    (net (code "42") (name "Net-(U$1-P1_1)") (class "Default")
      (node (ref "R4") (pin "2") (pinfunction "2_2") (pintype "passive"))
      (node (ref "U$1") (pin "23") (pinfunction "P1_1_23") (pintype "bidirectional"))
    )
    (net (code "43") (name "Net-(U$1-RESET#)") (class "Default")
      (node (ref "U$1") (pin "34") (pinfunction "RESET#_34") (pintype "bidirectional"))
      (node (ref "U$2") (pin "7") (pinfunction "7A_7") (pintype "bidirectional"))
    )
    (net (code "44") (name "Net-(U$3-BAT)") (class "Default")
      (node (ref "C21") (pin "1") (pinfunction "1_1") (pintype "passive"))
      (node (ref "R18") (pin "1") (pinfunction "1_1") (pintype "passive"))
      (node (ref "U$3") (pin "10") (pinfunction "BAT_10") (pintype "bidirectional"))
      (node (ref "U$3") (pin "9") (pinfunction "REGSRC_9") (pintype "bidirectional"))
    )
    (net (code "45") (name "Net-(U$3-CAP1)") (class "Default")
      (node (ref "C27") (pin "2") (pinfunction "2_2") (pintype "passive"))
      (node (ref "U$3") (pin "7") (pinfunction "CAP1_7") (pintype "bidirectional"))
    )
    (net (code "46") (name "Net-(U$3-SRN)") (class "Default")
      (node (ref "C22") (pin "1") (pinfunction "1_1") (pintype "passive"))
      (node (ref "C23") (pin "2") (pinfunction "2_2") (pintype "passive"))
      (node (ref "R19") (pin "1") (pinfunction "1_1") (pintype "passive"))
      (node (ref "U$3") (pin "19") (pinfunction "SRN_19") (pintype "bidirectional"))
    )
    (net (code "47") (name "Net-(U$3-SRP)") (class "Default")
      (node (ref "C22") (pin "2") (pinfunction "2_2") (pintype "passive"))
      (node (ref "C24") (pin "1") (pinfunction "1_1") (pintype "passive"))
      (node (ref "R20") (pin "1") (pinfunction "1_1") (pintype "passive"))
      (node (ref "U$3") (pin "18") (pinfunction "SRP_18") (pintype "bidirectional"))
    )
    (net (code "48") (name "Net-(U$5-BYPASS)") (class "Default")
      (node (ref "C2") (pin "1") (pinfunction "1_1") (pintype "passive"))
      (node (ref "U$5") (pin "4") (pinfunction "BYPASS_4") (pintype "bidirectional"))
    )
    (net (code "49") (name "Net-(U$9-P$1)") (class "Default")
      (node (ref "C31") (pin "1") (pinfunction "1_1") (pintype "passive"))
      (node (ref "Q1") (pin "2A") (pinfunction "S_2A") (pintype "bidirectional"))
      (node (ref "Q1") (pin "2B") (pinfunction "S_2B") (pintype "bidirectional"))
      (node (ref "Q1") (pin "2C") (pinfunction "S_2C") (pintype "bidirectional"))
      (node (ref "R19") (pin "2") (pinfunction "2_2") (pintype "passive"))
      (node (ref "R22") (pin "2") (pinfunction "2_2") (pintype "passive"))
      (node (ref "U$9") (pin "1") (pinfunction "P$1_1") (pintype "bidirectional"))
    )
    (net (code "50") (name "Net-(U$10-BAT)") (class "Default")
      (node (ref "C34") (pin "1") (pinfunction "1_1") (pintype "passive"))
      (node (ref "R42") (pin "1") (pinfunction "1_1") (pintype "passive"))
      (node (ref "R43") (pin "2") (pinfunction "2_2") (pintype "passive"))
      (node (ref "U$10") (pin "7") (pinfunction "BAT_7") (pintype "bidirectional"))
    )
    (net (code "51") (name "Net-(U$10-LED1)") (class "Default")
      (node (ref "LED4") (pin "C") (pinfunction "C_C") (pintype "passive"))
      (node (ref "U$10") (pin "16") (pinfunction "LED1_16") (pintype "bidirectional"))
    )
    (net (code "52") (name "Net-(U$10-LED2)") (class "Default")
      (node (ref "LED5") (pin "C") (pinfunction "C_C") (pintype "passive"))
      (node (ref "U$10") (pin "17") (pinfunction "LED2_17") (pintype "bidirectional"))
    )
    (net (code "53") (name "Net-(U$10-LED3)") (class "Default")
      (node (ref "LED6") (pin "C") (pinfunction "C_C") (pintype "passive"))
      (node (ref "U$10") (pin "18") (pinfunction "LED3_18") (pintype "bidirectional"))
    )
    (net (code "54") (name "Net-(U$10-LED4)") (class "Default")
      (node (ref "LED7") (pin "C") (pinfunction "C_C") (pintype "passive"))
      (node (ref "U$10") (pin "19") (pinfunction "LED4_19") (pintype "bidirectional"))
    )
    (net (code "55") (name "Net-(U$10-LED5)") (class "Default")
      (node (ref "LED8") (pin "C") (pinfunction "C_C") (pintype "passive"))
      (node (ref "U$10") (pin "20") (pinfunction "LED5_20") (pintype "bidirectional"))
    )
    (net (code "56") (name "Net-(U$10-MRST)") (class "Default")
      (node (ref "R36") (pin "1") (pinfunction "1_1") (pintype "passive"))
      (node (ref "U$10") (pin "24") (pinfunction "MRST_24") (pintype "bidirectional"))
    )
    (net (code "57") (name "Net-(U$10-PRECHG)") (class "Default")
      (node (ref "R35") (pin "2") (pinfunction "2_2") (pintype "passive"))
      (node (ref "U$10") (pin "5") (pinfunction "PRECHG_5") (pintype "bidirectional"))
    )
    (net (code "58") (name "Net-(U$10-RBI)") (class "Default")
      (node (ref "C33") (pin "2") (pinfunction "2_2") (pintype "passive"))
      (node (ref "U$10") (pin "27") (pinfunction "RBI_27") (pintype "bidirectional"))
    )
    (net (code "59") (name "Net-(U$10-SMBC)") (class "Default")
      (node (ref "R48") (pin "1") (pinfunction "1_1") (pintype "passive"))
      (node (ref "U$10") (pin "13") (pinfunction "SMBC_13") (pintype "bidirectional"))
    )
    (net (code "60") (name "Net-(U$10-SMBD)") (class "Default")
      (node (ref "R49") (pin "1") (pinfunction "1_1") (pintype "passive"))
      (node (ref "U$10") (pin "11") (pinfunction "SMBD_11") (pintype "bidirectional"))
    )
    (net (code "61") (name "P2_1") (class "Default")
      (node (ref "U$1") (pin "10") (pinfunction "P2_1_10") (pintype "bidirectional"))
      (node (ref "U$2") (pin "4") (pinfunction "4A_4") (pintype "bidirectional"))
    )
    (net (code "62") (name "P2_2") (class "Default")
      (node (ref "U$1") (pin "9") (pinfunction "P2_2_9") (pintype "bidirectional"))
      (node (ref "U$2") (pin "3") (pinfunction "3A_3") (pintype "bidirectional"))
    )
    (net (code "63") (name "PACK-") (class "Default")
      (node (ref "C32") (pin "2") (pinfunction "2_2") (pintype "passive"))
      (node (ref "C36") (pin "1") (pinfunction "1_1") (pintype "passive"))
      (node (ref "D3") (pin "P$1") (pinfunction "1_P$1") (pintype "bidirectional"))
      (node (ref "D7") (pin "1") (pinfunction "P$1_1") (pintype "bidirectional"))
      (node (ref "D8") (pin "P$1") (pinfunction "P$1_P$1") (pintype "bidirectional"))
      (node (ref "Q2") (pin "2A") (pinfunction "S_2A") (pintype "bidirectional"))
      (node (ref "Q2") (pin "2B") (pinfunction "S_2B") (pintype "bidirectional"))
      (node (ref "Q2") (pin "2C") (pinfunction "S_2C") (pintype "bidirectional"))
      (node (ref "Q4") (pin "2") (pinfunction "S_2") (pintype "bidirectional"))
      (node (ref "R23") (pin "2") (pinfunction "2_2") (pintype "passive"))
      (node (ref "R33") (pin "1") (pinfunction "1_1") (pintype "passive"))
      (node (ref "SP1") (pin "P$2") (pinfunction "P$2_P$2") (pintype "bidirectional"))
      (node (ref "SP2") (pin "P$1") (pinfunction "P$1_P$1") (pintype "bidirectional"))
    )
    (net (code "64") (name "PRECHARGE_CONTROL") (class "Default")
      (node (ref "Q5") (pin "1") (pinfunction "B_1") (pintype "bidirectional"))
      (node (ref "R35") (pin "1") (pinfunction "1_1") (pintype "passive"))
    )
    (net (code "65") (name "REGOUT") (class "Default")
      (node (ref "C28") (pin "1") (pinfunction "1_1") (pintype "passive"))
      (node (ref "C30") (pin "1") (pinfunction "1_1") (pintype "passive"))
      (node (ref "C35") (pin "2") (pinfunction "2_2") (pintype "passive"))
      (node (ref "Q5") (pin "2") (pinfunction "E_2") (pintype "bidirectional"))
      (node (ref "R26") (pin "1") (pinfunction "1_1") (pintype "passive"))
      (node (ref "R27") (pin "1") (pinfunction "1_1") (pintype "passive"))
      (node (ref "R36") (pin "2") (pinfunction "2_2") (pintype "passive"))
      (node (ref "R37") (pin "2") (pinfunction "2_2") (pintype "passive"))
      (node (ref "R38") (pin "2") (pinfunction "2_2") (pintype "passive"))
      (node (ref "R39") (pin "2") (pinfunction "2_2") (pintype "passive"))
      (node (ref "R40") (pin "2") (pinfunction "2_2") (pintype "passive"))
      (node (ref "R41") (pin "2") (pinfunction "2_2") (pintype "passive"))
      (node (ref "R44") (pin "1") (pinfunction "1_1") (pintype "passive"))
      (node (ref "R47") (pin "2") (pinfunction "2_2") (pintype "passive"))
      (node (ref "U$10") (pin "26") (pinfunction "VCC_26") (pintype "bidirectional"))
      (node (ref "U$3") (pin "8") (pinfunction "REGOUT_8") (pintype "bidirectional"))
      (node (ref "U$4") (pin "3") (pinfunction "3_3") (pintype "bidirectional"))
    )
    (net (code "66") (name "REG_IN") (class "Default")
      (node (ref "C4") (pin "1") (pinfunction "1_1") (pintype "passive"))
      (node (ref "U$4") (pin "2") (pinfunction "2_2") (pintype "bidirectional"))
      (node (ref "U$5") (pin "1") (pinfunction "VIN_1") (pintype "bidirectional"))
      (node (ref "U$5") (pin "3") (pinfunction "EN_3") (pintype "bidirectional"))
    )
    (net (code "67") (name "SCL") (class "Default")
      (node (ref "JP1") (pin "1") (pinfunction "1_1") (pintype "passive"))
      (node (ref "R1") (pin "2") (pinfunction "2_2") (pintype "passive"))
      (node (ref "U$1") (pin "14") (pinfunction "SCL_14") (pintype "bidirectional"))
      (node (ref "U$16") (pin "2") (pinfunction "2_2") (pintype "bidirectional"))
    )
    (net (code "68") (name "SCL_") (class "Default")
      (node (ref "R27") (pin "2") (pinfunction "2_2") (pintype "passive"))
      (node (ref "R55") (pin "2") (pinfunction "2_2") (pintype "passive"))
      (node (ref "U$3") (pin "5") (pinfunction "SCL_5") (pintype "bidirectional"))
    )
    (net (code "69") (name "SCL_BMS") (class "Default")
      (node (ref "R56") (pin "1") (pinfunction "1_1") (pintype "passive"))
      (node (ref "SP4") (pin "P$2") (pinfunction "P$2_P$2") (pintype "bidirectional"))
      (node (ref "U$10") (pin "4") (pinfunction "SCL_4") (pintype "bidirectional"))
    )
    (net (code "70") (name "SDA") (class "Default")
      (node (ref "JP1") (pin "2") (pinfunction "2_2") (pintype "passive"))
      (node (ref "R2") (pin "2") (pinfunction "2_2") (pintype "passive"))
      (node (ref "U$1") (pin "15") (pinfunction "SDA_15") (pintype "bidirectional"))
      (node (ref "U$17") (pin "2") (pinfunction "2_2") (pintype "bidirectional"))
    )
    (net (code "71") (name "SDA_") (class "Default")
      (node (ref "R26") (pin "2") (pinfunction "2_2") (pintype "passive"))
      (node (ref "R54") (pin "2") (pinfunction "2_2") (pintype "passive"))
      (node (ref "U$3") (pin "4") (pinfunction "SDA_4") (pintype "bidirectional"))
    )
    (net (code "72") (name "SDA_BMS") (class "Default")
      (node (ref "R57") (pin "1") (pinfunction "1_1") (pintype "passive"))
      (node (ref "SP3") (pin "P$2") (pinfunction "P$2_P$2") (pintype "bidirectional"))
      (node (ref "U$10") (pin "3") (pinfunction "SDA_3") (pintype "bidirectional"))
    )
    (net (code "73") (name "SMBC") (class "Default")
      (node (ref "R50") (pin "2") (pinfunction "2_2") (pintype "passive"))
      (node (ref "SP6") (pin "P$2") (pinfunction "P$2_P$2") (pintype "bidirectional"))
      (node (ref "U$16") (pin "1") (pinfunction "1_1") (pintype "bidirectional"))
    )
    (net (code "74") (name "SMBD") (class "Default")
      (node (ref "R51") (pin "2") (pinfunction "2_2") (pintype "passive"))
      (node (ref "SP5") (pin "P$1") (pinfunction "P$1_P$1") (pintype "bidirectional"))
      (node (ref "U$17") (pin "1") (pinfunction "1_1") (pintype "bidirectional"))
    )
    (net (code "75") (name "VC0") (class "Default")
      (node (ref "C20") (pin "2") (pinfunction "2_2") (pintype "passive"))
      (node (ref "R11") (pin "1") (pinfunction "1_1") (pintype "passive"))
      (node (ref "U$3") (pin "17") (pinfunction "VC0_17") (pintype "bidirectional"))
    )
    (net (code "76") (name "VC1") (class "Default")
      (node (ref "C15") (pin "2") (pinfunction "2_2") (pintype "passive"))
      (node (ref "C16") (pin "2") (pinfunction "2_2") (pintype "passive"))
      (node (ref "R12") (pin "1") (pinfunction "1_1") (pintype "passive"))
      (node (ref "U$3") (pin "16") (pinfunction "VC1_16") (pintype "bidirectional"))
    )
    (net (code "77") (name "VC2") (class "Default")
      (node (ref "C16") (pin "1") (pinfunction "1_1") (pintype "passive"))
      (node (ref "C17") (pin "2") (pinfunction "2_2") (pintype "passive"))
      (node (ref "R13") (pin "1") (pinfunction "1_1") (pintype "passive"))
      (node (ref "U$3") (pin "15") (pinfunction "VC2_15") (pintype "bidirectional"))
    )
    (net (code "78") (name "VC3") (class "Default")
      (node (ref "C17") (pin "1") (pinfunction "1_1") (pintype "passive"))
      (node (ref "C18") (pin "2") (pinfunction "2_2") (pintype "passive"))
      (node (ref "R14") (pin "1") (pinfunction "1_1") (pintype "passive"))
      (node (ref "U$3") (pin "14") (pinfunction "VC3_14") (pintype "bidirectional"))
    )
    (net (code "79") (name "VC4") (class "Default")
      (node (ref "C18") (pin "1") (pinfunction "1_1") (pintype "passive"))
      (node (ref "C19") (pin "2") (pinfunction "2_2") (pintype "passive"))
      (node (ref "R15") (pin "1") (pinfunction "1_1") (pintype "passive"))
      (node (ref "U$3") (pin "13") (pinfunction "VC4_13") (pintype "bidirectional"))
    )
    (net (code "80") (name "VC5") (class "Default")
      (node (ref "C19") (pin "1") (pinfunction "1_1") (pintype "passive"))
      (node (ref "R16") (pin "1") (pinfunction "1_1") (pintype "passive"))
      (node (ref "U$3") (pin "12") (pinfunction "VC5_12") (pintype "bidirectional"))
    )
    (net (code "81") (name "unconnected-(JP2-Pad2)") (class "Default")
      (node (ref "JP2") (pin "2") (pinfunction "2_2") (pintype "passive"))
    )
    (net (code "82") (name "unconnected-(U$1-NC-Pad16)") (class "Default")
      (node (ref "U$1") (pin "16") (pinfunction "NC_16") (pintype "bidirectional"))
    )
    (net (code "83") (name "unconnected-(U$1-NC2-Pad35)") (class "Default")
      (node (ref "U$1") (pin "35") (pinfunction "NC2_35") (pintype "bidirectional"))
    )
    (net (code "84") (name "unconnected-(U$1-P0_0-Pad33)") (class "Default")
      (node (ref "U$1") (pin "33") (pinfunction "P0_0_33") (pintype "bidirectional"))
    )
    (net (code "85") (name "unconnected-(U$1-P0_1-Pad32)") (class "Default")
      (node (ref "U$1") (pin "32") (pinfunction "P0_1_32") (pintype "bidirectional"))
    )
    (net (code "86") (name "unconnected-(U$1-P0_2-Pad31)") (class "Default")
      (node (ref "U$1") (pin "31") (pinfunction "P0_2_31") (pintype "bidirectional"))
    )
    (net (code "87") (name "unconnected-(U$1-P0_3-Pad30)") (class "Default")
      (node (ref "U$1") (pin "30") (pinfunction "P0_3_30") (pintype "bidirectional"))
    )
    (net (code "88") (name "unconnected-(U$1-P0_4-Pad29)") (class "Default")
      (node (ref "U$1") (pin "29") (pinfunction "P0_4_29") (pintype "bidirectional"))
    )
    (net (code "89") (name "unconnected-(U$1-P0_5-Pad28)") (class "Default")
      (node (ref "U$1") (pin "28") (pinfunction "P0_5_28") (pintype "bidirectional"))
    )
    (net (code "90") (name "unconnected-(U$1-P0_6-Pad27)") (class "Default")
      (node (ref "U$1") (pin "27") (pinfunction "P0_6_27") (pintype "bidirectional"))
    )
    (net (code "91") (name "unconnected-(U$1-P0_7-Pad26)") (class "Default")
      (node (ref "U$1") (pin "26") (pinfunction "P0_7_26") (pintype "bidirectional"))
    )
    (net (code "92") (name "unconnected-(U$1-P1_2-Pad22)") (class "Default")
      (node (ref "U$1") (pin "22") (pinfunction "P1_2_22") (pintype "bidirectional"))
    )
    (net (code "93") (name "unconnected-(U$1-P1_3-Pad21)") (class "Default")
      (node (ref "U$1") (pin "21") (pinfunction "P1_3_21") (pintype "bidirectional"))
    )
    (net (code "94") (name "unconnected-(U$1-P1_4-Pad20)") (class "Default")
      (node (ref "U$1") (pin "20") (pinfunction "P1_4_20") (pintype "bidirectional"))
    )
    (net (code "95") (name "unconnected-(U$1-P1_5-Pad19)") (class "Default")
      (node (ref "U$1") (pin "19") (pinfunction "P1_5_19") (pintype "bidirectional"))
    )
    (net (code "96") (name "unconnected-(U$1-P1_6-Pad13)") (class "Default")
      (node (ref "U$1") (pin "13") (pinfunction "P1_6_13") (pintype "bidirectional"))
    )
    (net (code "97") (name "unconnected-(U$1-P1_7-Pad12)") (class "Default")
      (node (ref "U$1") (pin "12") (pinfunction "P1_7_12") (pintype "bidirectional"))
    )
    (net (code "98") (name "unconnected-(U$1-P2_0-Pad11)") (class "Default")
      (node (ref "U$1") (pin "11") (pinfunction "P2_0_11") (pintype "bidirectional"))
    )
    (net (code "99") (name "unconnected-(U$2-5A-Pad5)") (class "Default")
      (node (ref "U$2") (pin "5") (pinfunction "5A_5") (pintype "bidirectional"))
    )
    (net (code "100") (name "unconnected-(U$2-6A-Pad6)") (class "Default")
      (node (ref "U$2") (pin "6") (pinfunction "6A_6") (pintype "bidirectional"))
    )
    (net (code "101") (name "unconnected-(U$2-8A-Pad8)") (class "Default")
      (node (ref "U$2") (pin "8") (pinfunction "8A_8") (pintype "bidirectional"))
    )
    (net (code "102") (name "unconnected-(U$2-9A-Pad9)") (class "Default")
      (node (ref "U$2") (pin "9") (pinfunction "9A_9") (pintype "bidirectional"))
    )
    (net (code "103") (name "unconnected-(U$2-10A-Pad10)") (class "Default")
      (node (ref "U$2") (pin "10") (pinfunction "10A_10") (pintype "bidirectional"))
    )
    (net (code "104") (name "unconnected-(U$10-ADREN-Pad29)") (class "Default")
      (node (ref "U$10") (pin "29") (pinfunction "ADREN_29") (pintype "bidirectional"))
    )
    (net (code "105") (name "unconnected-(U$10-COM-Pad1)") (class "Default")
      (node (ref "U$10") (pin "1") (pinfunction "COM_1") (pintype "bidirectional"))
    )
    (net (code "106") (name "unconnected-(U$10-PWRM-Pad15)") (class "Default")
      (node (ref "U$10") (pin "15") (pinfunction "PWRM_15") (pintype "bidirectional"))
    )
    (net (code "107") (name "unconnected-(U$10-SAFE-Pad10)") (class "Default")
      (node (ref "U$10") (pin "10") (pinfunction "SAFE_10") (pintype "bidirectional"))
    )
  )
)
